# Servo.net
KiCad netlist of a schematic drawn in Altium Designer
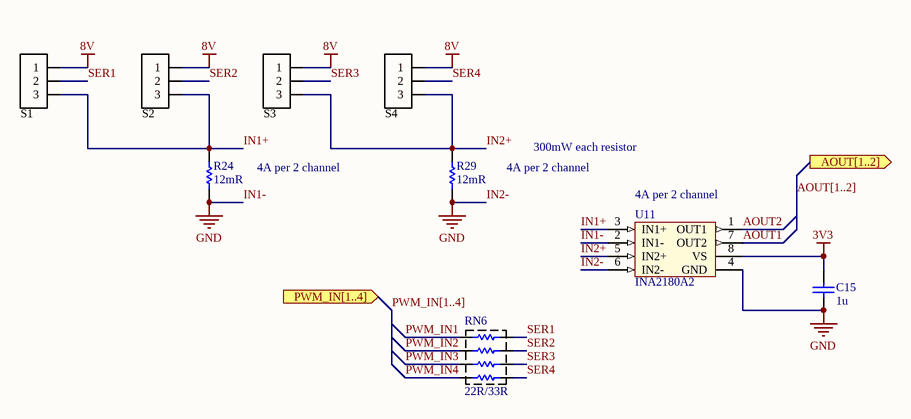
[diagram p0: Servo.SchDoc]

(export (version "E")
  (design (tool "Eeschema 10.0.6"))
  (components
    (comp (ref "C15")
      (value "1u")
      (footprint "CAPC1608X90N")
      (description "Capacitor")
      (fields (field (name "Comment") "Cap") (field (name "PUBLISHER") "Altium Limited"))
      (libsource (lib "IOBoard_Low") (part "Cap"))
    )
    (comp (ref "R24")
      (value "12mR")
      (footprint "RESC2012X70N")
      (description "Resistor")
      (fields (field (name "Comment") "Res1") (field (name "PUBLISHER") "Altium Limited"))
      (libsource (lib "IOBoard_Low") (part "Res1"))
    )
    (comp (ref "R29")
      (value "12mR")
      (footprint "RESC2012X70N")
      (description "Resistor")
      (fields (field (name "Comment") "Res1") (field (name "PUBLISHER") "Altium Limited"))
      (libsource (lib "IOBoard_Low") (part "Res1"))
    )
    (comp (ref "RN6")
      (value "22R/33R")
      (footprint "RESCAXS50P160X320X70-8N")
      (fields (field (name "Comment") "resistor network"))
      (libsource (lib "IOBoard") (part "RES_NET"))
    )
    (comp (ref "S1")
      (value "Header")
      (footprint "1x3POS_HEADER")
      (description "Header 3-pin")
      (libsource (lib "IOBoard") (part "Header3P"))
    )
    (comp (ref "S2")
      (value "Header")
      (footprint "1x3POS_HEADER")
      (description "Header 3-pin")
      (libsource (lib "IOBoard") (part "Header3P"))
    )
    (comp (ref "S3")
      (value "Header")
      (footprint "1x3POS_HEADER")
      (description "Header 3-pin")
      (libsource (lib "IOBoard") (part "Header3P"))
    )
    (comp (ref "S4")
      (value "Header")
      (footprint "1x3POS_HEADER")
      (description "Header 3-pin")
      (libsource (lib "IOBoard") (part "Header3P"))
    )
    (comp (ref "U11")
      (value "INA2180A2")
      (footprint "VSSOP8")
      (description "Dual channel current amplifier with 50V/V gain")
      (libsource (lib "IOBoard_Low") (part "INA2180A2"))
    )
  )
  (nets
    (net (code "1") (name "/AOUT1") (class "Default")
      (node (ref "U11") (pin "7") (pinfunction "OUT2_7") (pintype "output"))
    )
    (net (code "2") (name "/AOUT2") (class "Default")
      (node (ref "U11") (pin "1") (pinfunction "OUT1_1") (pintype "output"))
    )
    (net (code "4") (name "/IN1+") (class "Default")
      (node (ref "R24") (pin "2") (pinfunction "2_2") (pintype "passive"))
      (node (ref "S1") (pin "3") (pinfunction "3_3") (pintype "passive"))
      (node (ref "S2") (pin "3") (pinfunction "3_3") (pintype "passive"))
      (node (ref "U11") (pin "3") (pinfunction "IN1+_3") (pintype "input"))
    )
    (net (code "5") (name "/IN2+") (class "Default")
      (node (ref "R29") (pin "2") (pinfunction "2_2") (pintype "passive"))
      (node (ref "S3") (pin "3") (pinfunction "3_3") (pintype "passive"))
      (node (ref "S4") (pin "3") (pinfunction "3_3") (pintype "passive"))
      (node (ref "U11") (pin "5") (pinfunction "IN2+_5") (pintype "input"))
    )
    (net (code "6") (name "/PWM_IN1") (class "Default")
      (node (ref "RN6") (pin "1") (pinfunction "1_1") (pintype "power_in"))
    )
    (net (code "7") (name "/PWM_IN2") (class "Default")
      (node (ref "RN6") (pin "2") (pinfunction "2_2") (pintype "power_in"))
    )
    (net (code "8") (name "/PWM_IN3") (class "Default")
      (node (ref "RN6") (pin "3") (pinfunction "3_3") (pintype "power_in"))
    )
    (net (code "9") (name "/PWM_IN4") (class "Default")
      (node (ref "RN6") (pin "4") (pinfunction "4_4") (pintype "power_in"))
    )
    (net (code "11") (name "/SER1") (class "Default")
      (node (ref "RN6") (pin "8") (pinfunction "8_8") (pintype "power_in"))
      (node (ref "S1") (pin "2") (pinfunction "2_2") (pintype "passive"))
    )
    (net (code "12") (name "/SER2") (class "Default")
      (node (ref "RN6") (pin "7") (pinfunction "7_7") (pintype "power_in"))
      (node (ref "S2") (pin "2") (pinfunction "2_2") (pintype "passive"))
    )
    (net (code "13") (name "/SER3") (class "Default")
      (node (ref "RN6") (pin "6") (pinfunction "6_6") (pintype "power_in"))
      (node (ref "S3") (pin "2") (pinfunction "2_2") (pintype "passive"))
    )
    (net (code "14") (name "/SER4") (class "Default")
      (node (ref "RN6") (pin "5") (pinfunction "5_5") (pintype "power_in"))
      (node (ref "S4") (pin "2") (pinfunction "2_2") (pintype "passive"))
    )
    (net (code "15") (name "3V3") (class "Default")
      (node (ref "C15") (pin "2") (pinfunction "2_2") (pintype "passive"))
      (node (ref "U11") (pin "8") (pinfunction "VS_8") (pintype "power_in"))
    )
    (net (code "16") (name "8V") (class "Default")
      (node (ref "S1") (pin "1") (pinfunction "1_1") (pintype "passive"))
      (node (ref "S2") (pin "1") (pinfunction "1_1") (pintype "passive"))
      (node (ref "S3") (pin "1") (pinfunction "1_1") (pintype "passive"))
      (node (ref "S4") (pin "1") (pinfunction "1_1") (pintype "passive"))
    )
    (net (code "17") (name "GND") (class "Default")
      (node (ref "C15") (pin "1") (pinfunction "1_1") (pintype "passive"))
      (node (ref "R24") (pin "1") (pinfunction "1_1") (pintype "passive"))
      (node (ref "R29") (pin "1") (pinfunction "1_1") (pintype "passive"))
      (node (ref "U11") (pin "2") (pinfunction "IN1-_2") (pintype "input"))
      (node (ref "U11") (pin "4") (pinfunction "GND_4") (pintype "power_in"))
      (node (ref "U11") (pin "6") (pinfunction "IN2-_6") (pintype "input"))
    )
  )
)
